# design.net
KiCad netlist of a schematic drawn in Altium Designer
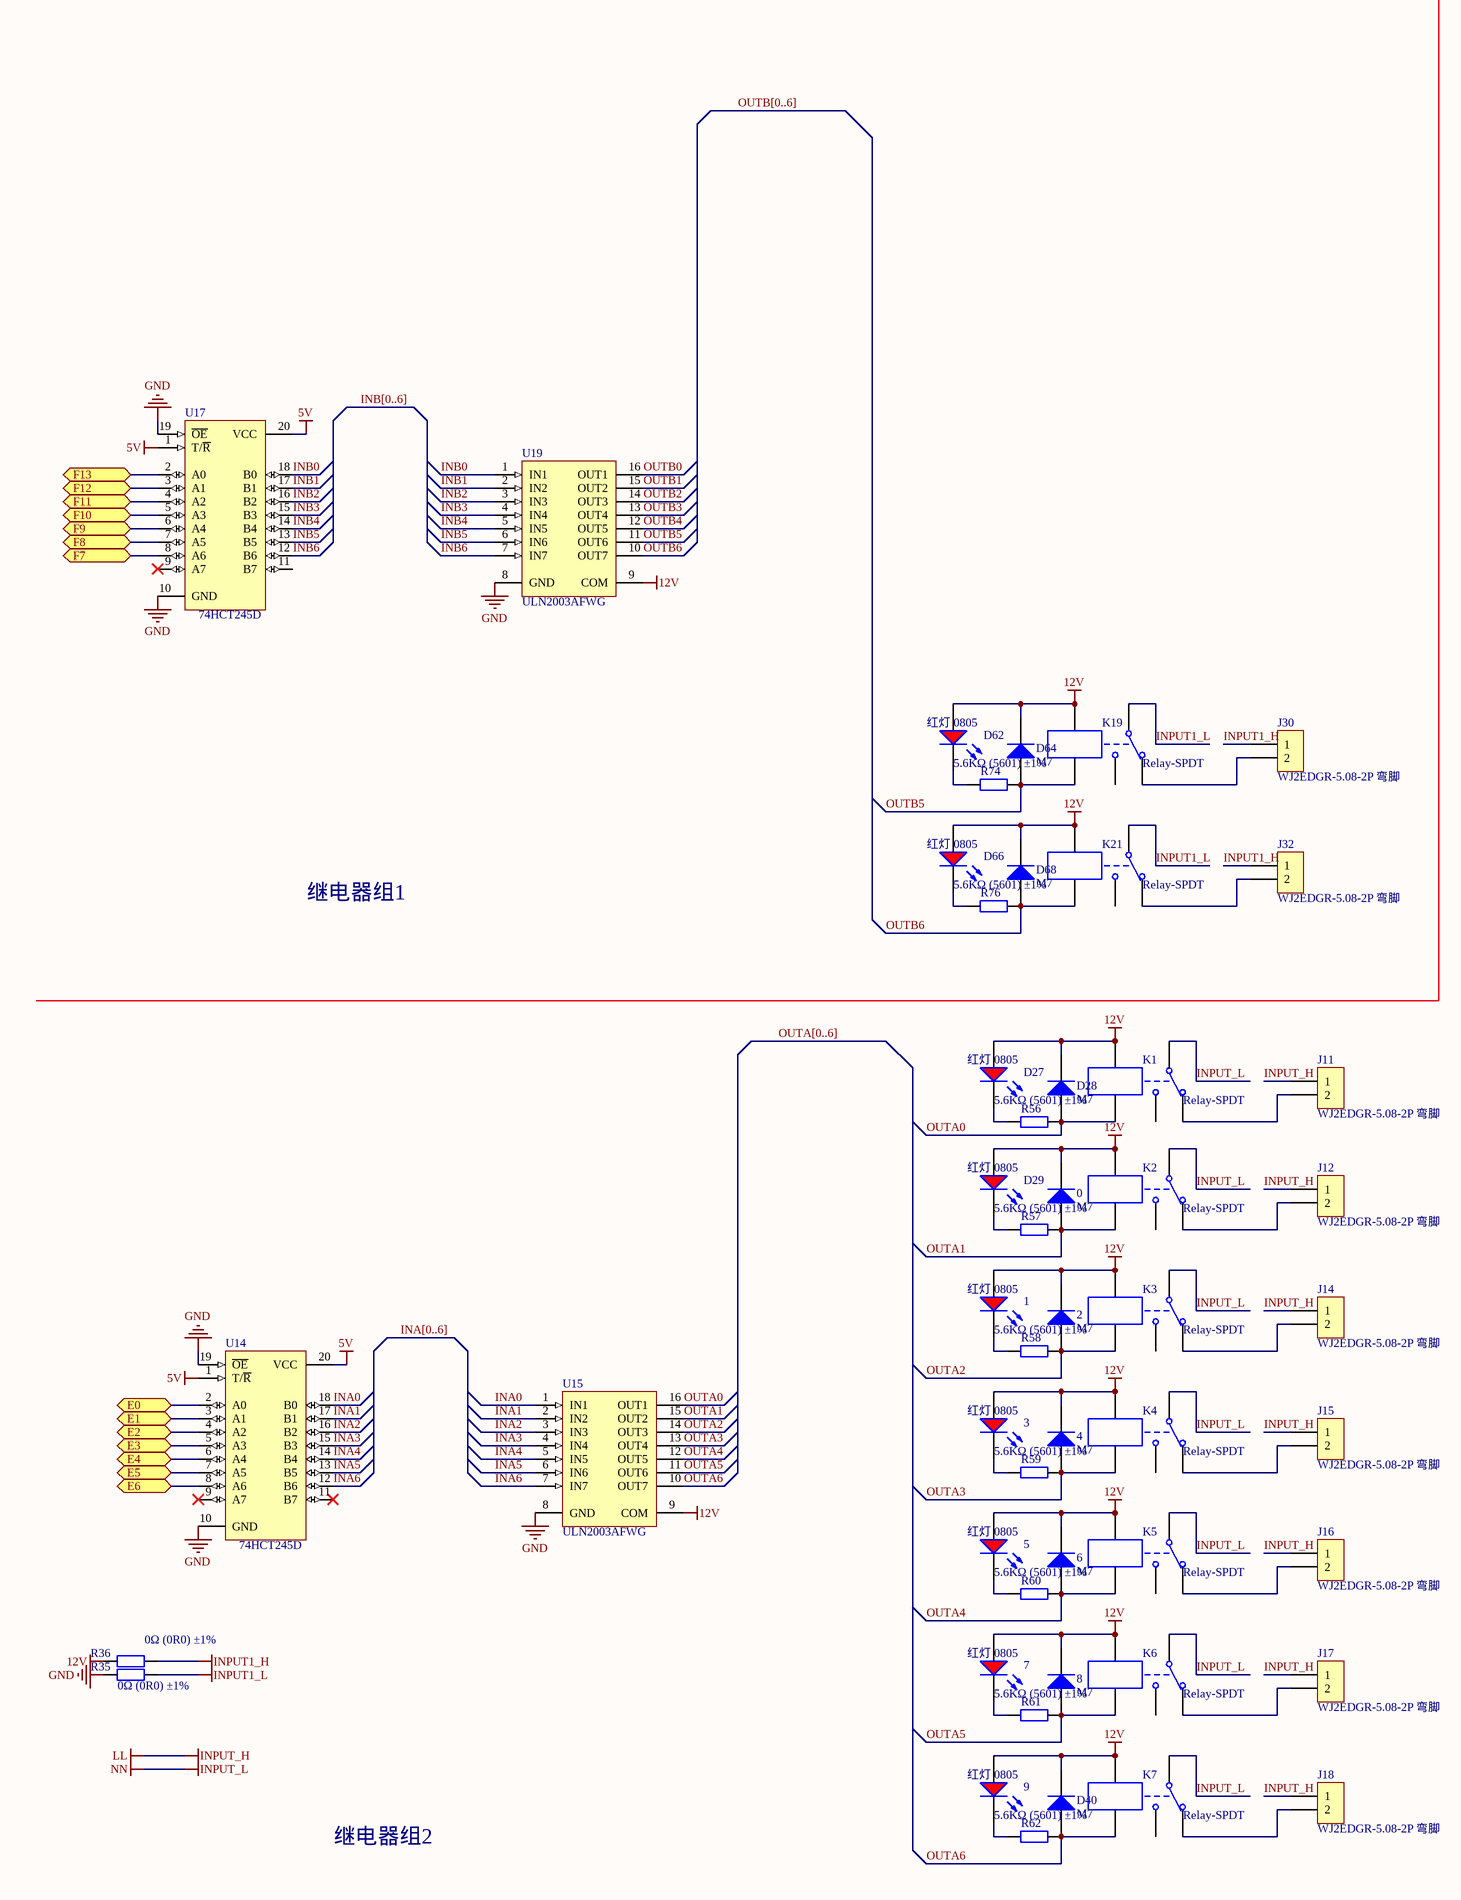
[diagram p0: 继电器驱动输出.SchDoc, left]
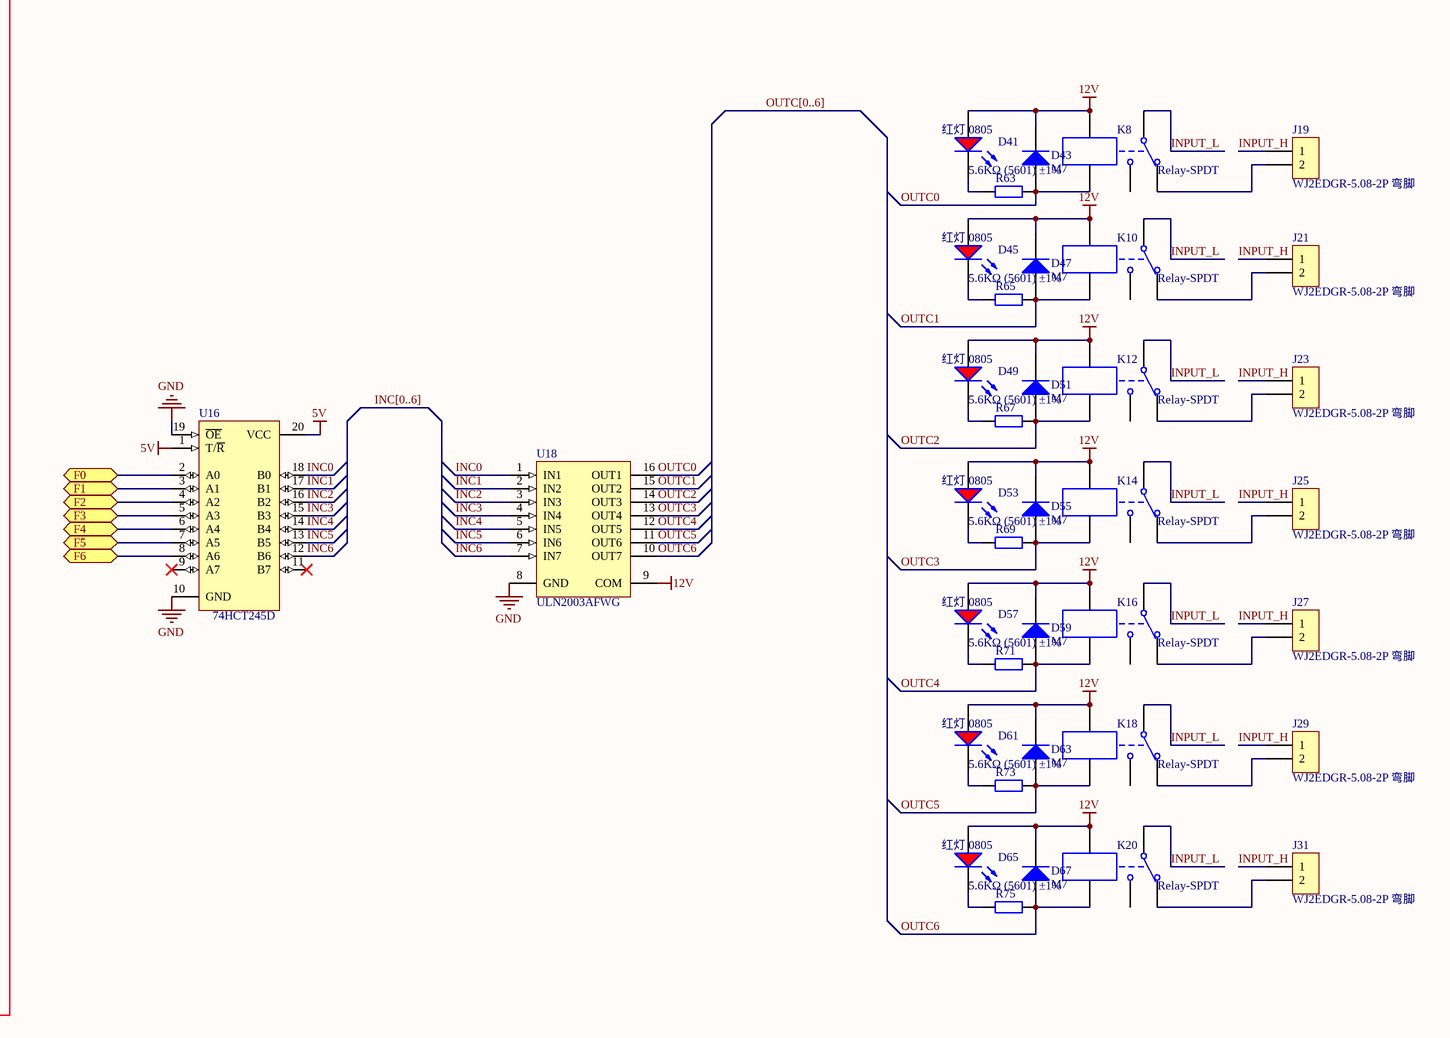
[diagram p1: 继电器驱动输出.SchDoc, right]

(export (version "E")
  (design (tool "Eeschema 10.0.6"))
  (components
    (comp (ref "0")
      (value "M7")
      (footprint "SMA(DO-214AC)_S1")
      (description "二极管")
      (libsource (lib "Diode") (part "SMA(DO-214AC) M7"))
    )
    (comp (ref "1")
      (value "红灯 0805")
      (footprint "0805_LED_S1")
      (description "发光二极管")
      (libsource (lib "LED") (part "0805 红灯"))
    )
    (comp (ref "2")
      (value "M7")
      (footprint "SMA(DO-214AC)_S1")
      (description "二极管")
      (libsource (lib "Diode") (part "SMA(DO-214AC) M7"))
    )
    (comp (ref "3")
      (value "红灯 0805")
      (footprint "0805_LED_S1")
      (description "发光二极管")
      (libsource (lib "LED") (part "0805 红灯"))
    )
    (comp (ref "4")
      (value "M7")
      (footprint "SMA(DO-214AC)_S1")
      (description "二极管")
      (libsource (lib "Diode") (part "SMA(DO-214AC) M7"))
    )
    (comp (ref "5")
      (value "红灯 0805")
      (footprint "0805_LED_S1")
      (description "发光二极管")
      (libsource (lib "LED") (part "0805 红灯"))
    )
    (comp (ref "6")
      (value "M7")
      (footprint "SMA(DO-214AC)_S1")
      (description "二极管")
      (libsource (lib "Diode") (part "SMA(DO-214AC) M7"))
    )
    (comp (ref "7")
      (value "红灯 0805")
      (footprint "0805_LED_S1")
      (description "发光二极管")
      (libsource (lib "LED") (part "0805 红灯"))
    )
    (comp (ref "8")
      (value "M7")
      (footprint "SMA(DO-214AC)_S1")
      (description "二极管")
      (libsource (lib "Diode") (part "SMA(DO-214AC) M7"))
    )
    (comp (ref "9")
      (value "红灯 0805")
      (footprint "0805_LED_S1")
      (description "发光二极管")
      (libsource (lib "LED") (part "0805 红灯"))
    )
    (comp (ref "D27")
      (value "红灯 0805")
      (footprint "0805_LED_S1")
      (description "发光二极管")
      (libsource (lib "LED") (part "0805 红灯"))
    )
    (comp (ref "D28")
      (value "M7")
      (footprint "SMA(DO-214AC)_S1")
      (description "二极管")
      (libsource (lib "Diode") (part "SMA(DO-214AC) M7"))
    )
    (comp (ref "D29")
      (value "红灯 0805")
      (footprint "0805_LED_S1")
      (description "发光二极管")
      (libsource (lib "LED") (part "0805 红灯"))
    )
    (comp (ref "D40")
      (value "M7")
      (footprint "SMA(DO-214AC)_S1")
      (description "二极管")
      (libsource (lib "Diode") (part "SMA(DO-214AC) M7"))
    )
    (comp (ref "D41")
      (value "红灯 0805")
      (footprint "0805_LED_S1")
      (description "发光二极管")
      (libsource (lib "LED") (part "0805 红灯"))
    )
    (comp (ref "D43")
      (value "M7")
      (footprint "SMA(DO-214AC)_S1")
      (description "二极管")
      (libsource (lib "Diode") (part "SMA(DO-214AC) M7"))
    )
    (comp (ref "D45")
      (value "红灯 0805")
      (footprint "0805_LED_S1")
      (description "发光二极管")
      (libsource (lib "LED") (part "0805 红灯"))
    )
    (comp (ref "D47")
      (value "M7")
      (footprint "SMA(DO-214AC)_S1")
      (description "二极管")
      (libsource (lib "Diode") (part "SMA(DO-214AC) M7"))
    )
    (comp (ref "D49")
      (value "红灯 0805")
      (footprint "0805_LED_S1")
      (description "发光二极管")
      (libsource (lib "LED") (part "0805 红灯"))
    )
    (comp (ref "D51")
      (value "M7")
      (footprint "SMA(DO-214AC)_S1")
      (description "二极管")
      (libsource (lib "Diode") (part "SMA(DO-214AC) M7"))
    )
    (comp (ref "D53")
      (value "红灯 0805")
      (footprint "0805_LED_S1")
      (description "发光二极管")
      (libsource (lib "LED") (part "0805 红灯"))
    )
    (comp (ref "D55")
      (value "M7")
      (footprint "SMA(DO-214AC)_S1")
      (description "二极管")
      (libsource (lib "Diode") (part "SMA(DO-214AC) M7"))
    )
    (comp (ref "D57")
      (value "红灯 0805")
      (footprint "0805_LED_S1")
      (description "发光二极管")
      (libsource (lib "LED") (part "0805 红灯"))
    )
    (comp (ref "D59")
      (value "M7")
      (footprint "SMA(DO-214AC)_S1")
      (description "二极管")
      (libsource (lib "Diode") (part "SMA(DO-214AC) M7"))
    )
    (comp (ref "D61")
      (value "红灯 0805")
      (footprint "0805_LED_S1")
      (description "发光二极管")
      (libsource (lib "LED") (part "0805 红灯"))
    )
    (comp (ref "D62")
      (value "红灯 0805")
      (footprint "0805_LED_S1")
      (description "发光二极管")
      (libsource (lib "LED") (part "0805 红灯"))
    )
    (comp (ref "D63")
      (value "M7")
      (footprint "SMA(DO-214AC)_S1")
      (description "二极管")
      (libsource (lib "Diode") (part "SMA(DO-214AC) M7"))
    )
    (comp (ref "D64")
      (value "M7")
      (footprint "SMA(DO-214AC)_S1")
      (description "二极管")
      (libsource (lib "Diode") (part "SMA(DO-214AC) M7"))
    )
    (comp (ref "D65")
      (value "红灯 0805")
      (footprint "0805_LED_S1")
      (description "发光二极管")
      (libsource (lib "LED") (part "0805 红灯"))
    )
    (comp (ref "D66")
      (value "红灯 0805")
      (footprint "0805_LED_S1")
      (description "发光二极管")
      (libsource (lib "LED") (part "0805 红灯"))
    )
    (comp (ref "D67")
      (value "M7")
      (footprint "SMA(DO-214AC)_S1")
      (description "二极管")
      (libsource (lib "Diode") (part "SMA(DO-214AC) M7"))
    )
    (comp (ref "D68")
      (value "M7")
      (footprint "SMA(DO-214AC)_S1")
      (description "二极管")
      (libsource (lib "Diode") (part "SMA(DO-214AC) M7"))
    )
    (comp (ref "J11")
      (value "WJ2EDGR-5.08-2P 弯脚")
      (footprint "Connector:WJ2EDGR-5.08-2")
      (description "2EDG连接器")
      (libsource (lib "Connector") (part "WJ2EDGR-5.08-2P 弯脚"))
    )
    (comp (ref "J12")
      (value "WJ2EDGR-5.08-2P 弯脚")
      (footprint "Connector:WJ2EDGR-5.08-2")
      (description "2EDG连接器")
      (libsource (lib "Connector") (part "WJ2EDGR-5.08-2P 弯脚"))
    )
    (comp (ref "J14")
      (value "WJ2EDGR-5.08-2P 弯脚")
      (footprint "Connector:WJ2EDGR-5.08-2")
      (description "2EDG连接器")
      (libsource (lib "Connector") (part "WJ2EDGR-5.08-2P 弯脚"))
    )
    (comp (ref "J15")
      (value "WJ2EDGR-5.08-2P 弯脚")
      (footprint "Connector:WJ2EDGR-5.08-2")
      (description "2EDG连接器")
      (libsource (lib "Connector") (part "WJ2EDGR-5.08-2P 弯脚"))
    )
    (comp (ref "J16")
      (value "WJ2EDGR-5.08-2P 弯脚")
      (footprint "Connector:WJ2EDGR-5.08-2")
      (description "2EDG连接器")
      (libsource (lib "Connector") (part "WJ2EDGR-5.08-2P 弯脚"))
    )
    (comp (ref "J17")
      (value "WJ2EDGR-5.08-2P 弯脚")
      (footprint "Connector:WJ2EDGR-5.08-2")
      (description "2EDG连接器")
      (libsource (lib "Connector") (part "WJ2EDGR-5.08-2P 弯脚"))
    )
    (comp (ref "J18")
      (value "WJ2EDGR-5.08-2P 弯脚")
      (footprint "Connector:WJ2EDGR-5.08-2")
      (description "2EDG连接器")
      (libsource (lib "Connector") (part "WJ2EDGR-5.08-2P 弯脚"))
    )
    (comp (ref "J19")
      (value "WJ2EDGR-5.08-2P 弯脚")
      (footprint "Connector:WJ2EDGR-5.08-2")
      (description "2EDG连接器")
      (libsource (lib "Connector") (part "WJ2EDGR-5.08-2P 弯脚"))
    )
    (comp (ref "J21")
      (value "WJ2EDGR-5.08-2P 弯脚")
      (footprint "Connector:WJ2EDGR-5.08-2")
      (description "2EDG连接器")
      (libsource (lib "Connector") (part "WJ2EDGR-5.08-2P 弯脚"))
    )
    (comp (ref "J23")
      (value "WJ2EDGR-5.08-2P 弯脚")
      (footprint "Connector:WJ2EDGR-5.08-2")
      (description "2EDG连接器")
      (libsource (lib "Connector") (part "WJ2EDGR-5.08-2P 弯脚"))
    )
    (comp (ref "J25")
      (value "WJ2EDGR-5.08-2P 弯脚")
      (footprint "Connector:WJ2EDGR-5.08-2")
      (description "2EDG连接器")
      (libsource (lib "Connector") (part "WJ2EDGR-5.08-2P 弯脚"))
    )
    (comp (ref "J27")
      (value "WJ2EDGR-5.08-2P 弯脚")
      (footprint "Connector:WJ2EDGR-5.08-2")
      (description "2EDG连接器")
      (libsource (lib "Connector") (part "WJ2EDGR-5.08-2P 弯脚"))
    )
    (comp (ref "J29")
      (value "WJ2EDGR-5.08-2P 弯脚")
      (footprint "Connector:WJ2EDGR-5.08-2")
      (description "2EDG连接器")
      (libsource (lib "Connector") (part "WJ2EDGR-5.08-2P 弯脚"))
    )
    (comp (ref "J30")
      (value "WJ2EDGR-5.08-2P 弯脚")
      (footprint "Connector:WJ2EDGR-5.08-2")
      (description "2EDG连接器")
      (libsource (lib "Connector") (part "WJ2EDGR-5.08-2P 弯脚"))
    )
    (comp (ref "J31")
      (value "WJ2EDGR-5.08-2P 弯脚")
      (footprint "Connector:WJ2EDGR-5.08-2")
      (description "2EDG连接器")
      (libsource (lib "Connector") (part "WJ2EDGR-5.08-2P 弯脚"))
    )
    (comp (ref "J32")
      (value "WJ2EDGR-5.08-2P 弯脚")
      (footprint "Connector:WJ2EDGR-5.08-2")
      (description "2EDG连接器")
      (libsource (lib "Connector") (part "WJ2EDGR-5.08-2P 弯脚"))
    )
    (comp (ref "K1")
      (value "Relay-SPDT")
      (footprint "继电器5脚")
      (description "Single-Pole Dual-Throw Relay")
      (fields (field (name "PUBLISHER") "Altium Limited"))
      (libsource (lib "Miscellaneous Devices") (part "Relay-SPDT"))
    )
    (comp (ref "K2")
      (value "Relay-SPDT")
      (footprint "继电器5脚")
      (description "Single-Pole Dual-Throw Relay")
      (fields (field (name "PUBLISHER") "Altium Limited"))
      (libsource (lib "Miscellaneous Devices") (part "Relay-SPDT"))
    )
    (comp (ref "K3")
      (value "Relay-SPDT")
      (footprint "继电器5脚")
      (description "Single-Pole Dual-Throw Relay")
      (fields (field (name "PUBLISHER") "Altium Limited"))
      (libsource (lib "Miscellaneous Devices") (part "Relay-SPDT"))
    )
    (comp (ref "K4")
      (value "Relay-SPDT")
      (footprint "继电器5脚")
      (description "Single-Pole Dual-Throw Relay")
      (fields (field (name "PUBLISHER") "Altium Limited"))
      (libsource (lib "Miscellaneous Devices") (part "Relay-SPDT"))
    )
    (comp (ref "K5")
      (value "Relay-SPDT")
      (footprint "继电器5脚")
      (description "Single-Pole Dual-Throw Relay")
      (fields (field (name "PUBLISHER") "Altium Limited"))
      (libsource (lib "Miscellaneous Devices") (part "Relay-SPDT"))
    )
    (comp (ref "K6")
      (value "Relay-SPDT")
      (footprint "继电器5脚")
      (description "Single-Pole Dual-Throw Relay")
      (fields (field (name "PUBLISHER") "Altium Limited"))
      (libsource (lib "Miscellaneous Devices") (part "Relay-SPDT"))
    )
    (comp (ref "K7")
      (value "Relay-SPDT")
      (footprint "继电器5脚")
      (description "Single-Pole Dual-Throw Relay")
      (fields (field (name "PUBLISHER") "Altium Limited"))
      (libsource (lib "Miscellaneous Devices") (part "Relay-SPDT"))
    )
    (comp (ref "K8")
      (value "Relay-SPDT")
      (footprint "继电器5脚")
      (description "Single-Pole Dual-Throw Relay")
      (fields (field (name "PUBLISHER") "Altium Limited"))
      (libsource (lib "Miscellaneous Devices") (part "Relay-SPDT"))
    )
    (comp (ref "K10")
      (value "Relay-SPDT")
      (footprint "继电器5脚")
      (description "Single-Pole Dual-Throw Relay")
      (fields (field (name "PUBLISHER") "Altium Limited"))
      (libsource (lib "Miscellaneous Devices") (part "Relay-SPDT"))
    )
    (comp (ref "K12")
      (value "Relay-SPDT")
      (footprint "继电器5脚")
      (description "Single-Pole Dual-Throw Relay")
      (fields (field (name "PUBLISHER") "Altium Limited"))
      (libsource (lib "Miscellaneous Devices") (part "Relay-SPDT"))
    )
    (comp (ref "K14")
      (value "Relay-SPDT")
      (footprint "继电器5脚")
      (description "Single-Pole Dual-Throw Relay")
      (fields (field (name "PUBLISHER") "Altium Limited"))
      (libsource (lib "Miscellaneous Devices") (part "Relay-SPDT"))
    )
    (comp (ref "K16")
      (value "Relay-SPDT")
      (footprint "继电器5脚")
      (description "Single-Pole Dual-Throw Relay")
      (fields (field (name "PUBLISHER") "Altium Limited"))
      (libsource (lib "Miscellaneous Devices") (part "Relay-SPDT"))
    )
    (comp (ref "K18")
      (value "Relay-SPDT")
      (footprint "继电器5脚")
      (description "Single-Pole Dual-Throw Relay")
      (fields (field (name "PUBLISHER") "Altium Limited"))
      (libsource (lib "Miscellaneous Devices") (part "Relay-SPDT"))
    )
    (comp (ref "K19")
      (value "Relay-SPDT")
      (footprint "继电器5脚")
      (description "Single-Pole Dual-Throw Relay")
      (fields (field (name "PUBLISHER") "Altium Limited"))
      (libsource (lib "Miscellaneous Devices") (part "Relay-SPDT"))
    )
    (comp (ref "K20")
      (value "Relay-SPDT")
      (footprint "继电器5脚")
      (description "Single-Pole Dual-Throw Relay")
      (fields (field (name "PUBLISHER") "Altium Limited"))
      (libsource (lib "Miscellaneous Devices") (part "Relay-SPDT"))
    )
    (comp (ref "K21")
      (value "Relay-SPDT")
      (footprint "继电器5脚")
      (description "Single-Pole Dual-Throw Relay")
      (fields (field (name "PUBLISHER") "Altium Limited"))
      (libsource (lib "Miscellaneous Devices") (part "Relay-SPDT"))
    )
    (comp (ref "R35")
      (value "0Ω (0R0) ±1%")
      (footprint "1206_R")
      (description "贴片电阻")
      (libsource (lib "RES") (part "1206 0Ω (0R0) 1%"))
    )
    (comp (ref "R36")
      (value "0Ω (0R0) ±1%")
      (footprint "1206_R")
      (description "贴片电阻")
      (libsource (lib "RES") (part "1206 0Ω (0R0) 1%"))
    )
    (comp (ref "R56")
      (value "5.6KΩ (5601) ±1%")
      (footprint "0805_R")
      (description "贴片电阻")
      (libsource (lib "RES") (part "0805 5.6KΩ (5601) 1%"))
    )
    (comp (ref "R57")
      (value "5.6KΩ (5601) ±1%")
      (footprint "0805_R")
      (description "贴片电阻")
      (libsource (lib "RES") (part "0805 5.6KΩ (5601) 1%"))
    )
    (comp (ref "R58")
      (value "5.6KΩ (5601) ±1%")
      (footprint "0805_R")
      (description "贴片电阻")
      (libsource (lib "RES") (part "0805 5.6KΩ (5601) 1%"))
    )
    (comp (ref "R59")
      (value "5.6KΩ (5601) ±1%")
      (footprint "0805_R")
      (description "贴片电阻")
      (libsource (lib "RES") (part "0805 5.6KΩ (5601) 1%"))
    )
    (comp (ref "R60")
      (value "5.6KΩ (5601) ±1%")
      (footprint "0805_R")
      (description "贴片电阻")
      (libsource (lib "RES") (part "0805 5.6KΩ (5601) 1%"))
    )
    (comp (ref "R61")
      (value "5.6KΩ (5601) ±1%")
      (footprint "0805_R")
      (description "贴片电阻")
      (libsource (lib "RES") (part "0805 5.6KΩ (5601) 1%"))
    )
    (comp (ref "R62")
      (value "5.6KΩ (5601) ±1%")
      (footprint "0805_R")
      (description "贴片电阻")
      (libsource (lib "RES") (part "0805 5.6KΩ (5601) 1%"))
    )
    (comp (ref "R63")
      (value "5.6KΩ (5601) ±1%")
      (footprint "0805_R")
      (description "贴片电阻")
      (libsource (lib "RES") (part "0805 5.6KΩ (5601) 1%"))
    )
    (comp (ref "R65")
      (value "5.6KΩ (5601) ±1%")
      (footprint "0805_R")
      (description "贴片电阻")
      (libsource (lib "RES") (part "0805 5.6KΩ (5601) 1%"))
    )
    (comp (ref "R67")
      (value "5.6KΩ (5601) ±1%")
      (footprint "0805_R")
      (description "贴片电阻")
      (libsource (lib "RES") (part "0805 5.6KΩ (5601) 1%"))
    )
    (comp (ref "R69")
      (value "5.6KΩ (5601) ±1%")
      (footprint "0805_R")
      (description "贴片电阻")
      (libsource (lib "RES") (part "0805 5.6KΩ (5601) 1%"))
    )
    (comp (ref "R71")
      (value "5.6KΩ (5601) ±1%")
      (footprint "0805_R")
      (description "贴片电阻")
      (libsource (lib "RES") (part "0805 5.6KΩ (5601) 1%"))
    )
    (comp (ref "R73")
      (value "5.6KΩ (5601) ±1%")
      (footprint "0805_R")
      (description "贴片电阻")
      (libsource (lib "RES") (part "0805 5.6KΩ (5601) 1%"))
    )
    (comp (ref "R74")
      (value "5.6KΩ (5601) ±1%")
      (footprint "0805_R")
      (description "贴片电阻")
      (libsource (lib "RES") (part "0805 5.6KΩ (5601) 1%"))
    )
    (comp (ref "R75")
      (value "5.6KΩ (5601) ±1%")
      (footprint "0805_R")
      (description "贴片电阻")
      (libsource (lib "RES") (part "0805 5.6KΩ (5601) 1%"))
    )
    (comp (ref "R76")
      (value "5.6KΩ (5601) ±1%")
      (footprint "0805_R")
      (description "贴片电阻")
      (libsource (lib "RES") (part "0805 5.6KΩ (5601) 1%"))
    )
    (comp (ref "U14")
      (value "74HCT245D")
      (footprint "SOIC-20_300mil")
      (description "74系列逻辑芯片")
      (libsource (lib "IC") (part "74HC245D_[C5625]"))
    )
    (comp (ref "U15")
      (value "ULN2003AFWG")
      (footprint "SOIC-16_150mil")
      (description "大电流驱动")
      (libsource (lib "IC") (part "ULN2003AFWG_[C5437]"))
    )
    (comp (ref "U16")
      (value "74HCT245D")
      (footprint "SOIC-20_300mil")
      (description "74系列逻辑芯片")
      (libsource (lib "IC") (part "74HC245D_[C5625]"))
    )
    (comp (ref "U17")
      (value "74HCT245D")
      (footprint "SOIC-20_300mil")
      (description "74系列逻辑芯片")
      (libsource (lib "IC") (part "74HC245D_[C5625]"))
    )
    (comp (ref "U18")
      (value "ULN2003AFWG")
      (footprint "SOIC-16_150mil")
      (description "大电流驱动")
      (libsource (lib "IC") (part "ULN2003AFWG_[C5437]"))
    )
    (comp (ref "U19")
      (value "ULN2003AFWG")
      (footprint "SOIC-16_150mil")
      (description "大电流驱动")
      (libsource (lib "IC") (part "ULN2003AFWG_[C5437]"))
    )
  )
  (nets
    (net (code "1") (name "/E0") (class "Default")
      (node (ref "U14") (pin "2") (pinfunction "A0_2") (pintype "bidirectional"))
    )
    (net (code "2") (name "/E1") (class "Default")
      (node (ref "U14") (pin "3") (pinfunction "A1_3") (pintype "bidirectional"))
    )
    (net (code "3") (name "/E2") (class "Default")
      (node (ref "U14") (pin "4") (pinfunction "A2_4") (pintype "bidirectional"))
    )
    (net (code "4") (name "/E3") (class "Default")
      (node (ref "U14") (pin "5") (pinfunction "A3_5") (pintype "bidirectional"))
    )
    (net (code "5") (name "/E4") (class "Default")
      (node (ref "U14") (pin "6") (pinfunction "A4_6") (pintype "bidirectional"))
    )
    (net (code "6") (name "/E5") (class "Default")
      (node (ref "U14") (pin "7") (pinfunction "A5_7") (pintype "bidirectional"))
    )
    (net (code "7") (name "/E6") (class "Default")
      (node (ref "U14") (pin "8") (pinfunction "A6_8") (pintype "bidirectional"))
    )
    (net (code "8") (name "/F0") (class "Default")
      (node (ref "U16") (pin "2") (pinfunction "A0_2") (pintype "bidirectional"))
    )
    (net (code "9") (name "/F1") (class "Default")
      (node (ref "U16") (pin "3") (pinfunction "A1_3") (pintype "bidirectional"))
    )
    (net (code "10") (name "/F2") (class "Default")
      (node (ref "U16") (pin "4") (pinfunction "A2_4") (pintype "bidirectional"))
    )
    (net (code "11") (name "/F3") (class "Default")
      (node (ref "U16") (pin "5") (pinfunction "A3_5") (pintype "bidirectional"))
    )
    (net (code "12") (name "/F4") (class "Default")
      (node (ref "U16") (pin "6") (pinfunction "A4_6") (pintype "bidirectional"))
    )
    (net (code "13") (name "/F5") (class "Default")
      (node (ref "U16") (pin "7") (pinfunction "A5_7") (pintype "bidirectional"))
    )
    (net (code "14") (name "/F6") (class "Default")
      (node (ref "U16") (pin "8") (pinfunction "A6_8") (pintype "bidirectional"))
    )
    (net (code "15") (name "/F7") (class "Default")
      (node (ref "U17") (pin "8") (pinfunction "A6_8") (pintype "bidirectional"))
    )
    (net (code "16") (name "/F8") (class "Default")
      (node (ref "U17") (pin "7") (pinfunction "A5_7") (pintype "bidirectional"))
    )
    (net (code "17") (name "/F9") (class "Default")
      (node (ref "U17") (pin "6") (pinfunction "A4_6") (pintype "bidirectional"))
    )
    (net (code "18") (name "/F10") (class "Default")
      (node (ref "U17") (pin "5") (pinfunction "A3_5") (pintype "bidirectional"))
    )
    (net (code "19") (name "/F11") (class "Default")
      (node (ref "U17") (pin "4") (pinfunction "A2_4") (pintype "bidirectional"))
    )
    (net (code "20") (name "/F12") (class "Default")
      (node (ref "U17") (pin "3") (pinfunction "A1_3") (pintype "bidirectional"))
    )
    (net (code "21") (name "/F13") (class "Default")
      (node (ref "U17") (pin "2") (pinfunction "A0_2") (pintype "bidirectional"))
    )
    (net (code "22") (name "/INA0") (class "Default")
      (node (ref "U14") (pin "18") (pinfunction "B0_18") (pintype "bidirectional"))
      (node (ref "U15") (pin "1") (pinfunction "IN1_1") (pintype "input"))
    )
    (net (code "23") (name "/INA1") (class "Default")
      (node (ref "U14") (pin "17") (pinfunction "B1_17") (pintype "bidirectional"))
      (node (ref "U15") (pin "2") (pinfunction "IN2_2") (pintype "input"))
    )
    (net (code "24") (name "/INA2") (class "Default")
      (node (ref "U14") (pin "16") (pinfunction "B2_16") (pintype "bidirectional"))
      (node (ref "U15") (pin "3") (pinfunction "IN3_3") (pintype "input"))
    )
    (net (code "25") (name "/INA3") (class "Default")
      (node (ref "U14") (pin "15") (pinfunction "B3_15") (pintype "bidirectional"))
      (node (ref "U15") (pin "4") (pinfunction "IN4_4") (pintype "input"))
    )
    (net (code "26") (name "/INA4") (class "Default")
      (node (ref "U14") (pin "14") (pinfunction "B4_14") (pintype "bidirectional"))
      (node (ref "U15") (pin "5") (pinfunction "IN5_5") (pintype "input"))
    )
    (net (code "27") (name "/INA5") (class "Default")
      (node (ref "U14") (pin "13") (pinfunction "B5_13") (pintype "bidirectional"))
      (node (ref "U15") (pin "6") (pinfunction "IN6_6") (pintype "input"))
    )
    (net (code "28") (name "/INA6") (class "Default")
      (node (ref "U14") (pin "12") (pinfunction "B6_12") (pintype "bidirectional"))
      (node (ref "U15") (pin "7") (pinfunction "IN7_7") (pintype "input"))
    )
    (net (code "30") (name "/INB0") (class "Default")
      (node (ref "U17") (pin "18") (pinfunction "B0_18") (pintype "bidirectional"))
      (node (ref "U19") (pin "1") (pinfunction "IN1_1") (pintype "input"))
    )
    (net (code "31") (name "/INB1") (class "Default")
      (node (ref "U17") (pin "17") (pinfunction "B1_17") (pintype "bidirectional"))
      (node (ref "U19") (pin "2") (pinfunction "IN2_2") (pintype "input"))
    )
    (net (code "32") (name "/INB2") (class "Default")
      (node (ref "U17") (pin "16") (pinfunction "B2_16") (pintype "bidirectional"))
      (node (ref "U19") (pin "3") (pinfunction "IN3_3") (pintype "input"))
    )
    (net (code "33") (name "/INB3") (class "Default")
      (node (ref "U17") (pin "15") (pinfunction "B3_15") (pintype "bidirectional"))
      (node (ref "U19") (pin "4") (pinfunction "IN4_4") (pintype "input"))
    )
    (net (code "34") (name "/INB4") (class "Default")
      (node (ref "U17") (pin "14") (pinfunction "B4_14") (pintype "bidirectional"))
      (node (ref "U19") (pin "5") (pinfunction "IN5_5") (pintype "input"))
    )
    (net (code "35") (name "/INB5") (class "Default")
      (node (ref "U17") (pin "13") (pinfunction "B5_13") (pintype "bidirectional"))
      (node (ref "U19") (pin "6") (pinfunction "IN6_6") (pintype "input"))
    )
    (net (code "36") (name "/INB6") (class "Default")
      (node (ref "U17") (pin "12") (pinfunction "B6_12") (pintype "bidirectional"))
      (node (ref "U19") (pin "7") (pinfunction "IN7_7") (pintype "input"))
    )
    (net (code "38") (name "/INC0") (class "Default")
      (node (ref "U16") (pin "18") (pinfunction "B0_18") (pintype "bidirectional"))
      (node (ref "U18") (pin "1") (pinfunction "IN1_1") (pintype "input"))
    )
    (net (code "39") (name "/INC1") (class "Default")
      (node (ref "U16") (pin "17") (pinfunction "B1_17") (pintype "bidirectional"))
      (node (ref "U18") (pin "2") (pinfunction "IN2_2") (pintype "input"))
    )
    (net (code "40") (name "/INC2") (class "Default")
      (node (ref "U16") (pin "16") (pinfunction "B2_16") (pintype "bidirectional"))
      (node (ref "U18") (pin "3") (pinfunction "IN3_3") (pintype "input"))
    )
    (net (code "41") (name "/INC3") (class "Default")
      (node (ref "U16") (pin "15") (pinfunction "B3_15") (pintype "bidirectional"))
      (node (ref "U18") (pin "4") (pinfunction "IN4_4") (pintype "input"))
    )
    (net (code "42") (name "/INC4") (class "Default")
      (node (ref "U16") (pin "14") (pinfunction "B4_14") (pintype "bidirectional"))
      (node (ref "U18") (pin "5") (pinfunction "IN5_5") (pintype "input"))
    )
    (net (code "43") (name "/INC5") (class "Default")
      (node (ref "U16") (pin "13") (pinfunction "B5_13") (pintype "bidirectional"))
      (node (ref "U18") (pin "6") (pinfunction "IN6_6") (pintype "input"))
    )
    (net (code "44") (name "/INC6") (class "Default")
      (node (ref "U16") (pin "12") (pinfunction "B6_12") (pintype "bidirectional"))
      (node (ref "U18") (pin "7") (pinfunction "IN7_7") (pintype "input"))
    )
    (net (code "46") (name "/OUTA0") (class "Default")
      (node (ref "D28") (pin "1") (pinfunction "A_1") (pintype "passive"))
      (node (ref "K1") (pin "5") (pinfunction "5_5") (pintype "passive"))
      (node (ref "R56") (pin "2") (pinfunction "2_2") (pintype "passive"))
      (node (ref "U15") (pin "16") (pinfunction "OUT1_16") (pintype "open_collector"))
    )
    (net (code "47") (name "/OUTA1") (class "Default")
      (node (ref "0") (pin "1") (pinfunction "A_1") (pintype "passive"))
      (node (ref "K2") (pin "5") (pinfunction "5_5") (pintype "passive"))
      (node (ref "R57") (pin "2") (pinfunction "2_2") (pintype "passive"))
      (node (ref "U15") (pin "15") (pinfunction "OUT2_15") (pintype "open_collector"))
    )
    (net (code "48") (name "/OUTA2") (class "Default")
      (node (ref "2") (pin "1") (pinfunction "A_1") (pintype "passive"))
      (node (ref "K3") (pin "5") (pinfunction "5_5") (pintype "passive"))
      (node (ref "R58") (pin "2") (pinfunction "2_2") (pintype "passive"))
      (node (ref "U15") (pin "14") (pinfunction "OUT3_14") (pintype "open_collector"))
    )
    (net (code "49") (name "/OUTA3") (class "Default")
      (node (ref "4") (pin "1") (pinfunction "A_1") (pintype "passive"))
      (node (ref "K4") (pin "5") (pinfunction "5_5") (pintype "passive"))
      (node (ref "R59") (pin "2") (pinfunction "2_2") (pintype "passive"))
      (node (ref "U15") (pin "13") (pinfunction "OUT4_13") (pintype "open_collector"))
    )
    (net (code "50") (name "/OUTA4") (class "Default")
      (node (ref "6") (pin "1") (pinfunction "A_1") (pintype "passive"))
      (node (ref "K5") (pin "5") (pinfunction "5_5") (pintype "passive"))
      (node (ref "R60") (pin "2") (pinfunction "2_2") (pintype "passive"))
      (node (ref "U15") (pin "12") (pinfunction "OUT5_12") (pintype "open_collector"))
    )
    (net (code "51") (name "/OUTA5") (class "Default")
      (node (ref "8") (pin "1") (pinfunction "A_1") (pintype "passive"))
      (node (ref "K6") (pin "5") (pinfunction "5_5") (pintype "passive"))
      (node (ref "R61") (pin "2") (pinfunction "2_2") (pintype "passive"))
      (node (ref "U15") (pin "11") (pinfunction "OUT6_11") (pintype "open_collector"))
    )
    (net (code "52") (name "/OUTA6") (class "Default")
      (node (ref "D40") (pin "1") (pinfunction "A_1") (pintype "passive"))
      (node (ref "K7") (pin "5") (pinfunction "5_5") (pintype "passive"))
      (node (ref "R62") (pin "2") (pinfunction "2_2") (pintype "passive"))
      (node (ref "U15") (pin "10") (pinfunction "OUT7_10") (pintype "open_collector"))
    )
    (net (code "54") (name "/OUTB0") (class "Default")
      (node (ref "U19") (pin "16") (pinfunction "OUT1_16") (pintype "open_collector"))
    )
    (net (code "55") (name "/OUTB1") (class "Default")
      (node (ref "U19") (pin "15") (pinfunction "OUT2_15") (pintype "open_collector"))
    )
    (net (code "56") (name "/OUTB2") (class "Default")
      (node (ref "U19") (pin "14") (pinfunction "OUT3_14") (pintype "open_collector"))
    )
    (net (code "57") (name "/OUTB3") (class "Default")
      (node (ref "U19") (pin "13") (pinfunction "OUT4_13") (pintype "open_collector"))
    )
    (net (code "58") (name "/OUTB4") (class "Default")
      (node (ref "U19") (pin "12") (pinfunction "OUT5_12") (pintype "open_collector"))
    )
    (net (code "59") (name "/OUTB5") (class "Default")
      (node (ref "D64") (pin "1") (pinfunction "A_1") (pintype "passive"))
      (node (ref "K19") (pin "5") (pinfunction "5_5") (pintype "passive"))
      (node (ref "R74") (pin "2") (pinfunction "2_2") (pintype "passive"))
      (node (ref "U19") (pin "11") (pinfunction "OUT6_11") (pintype "open_collector"))
    )
    (net (code "60") (name "/OUTB6") (class "Default")
      (node (ref "D68") (pin "1") (pinfunction "A_1") (pintype "passive"))
      (node (ref "K21") (pin "5") (pinfunction "5_5") (pintype "passive"))
      (node (ref "R76") (pin "2") (pinfunction "2_2") (pintype "passive"))
      (node (ref "U19") (pin "10") (pinfunction "OUT7_10") (pintype "open_collector"))
    )
    (net (code "62") (name "/OUTC0") (class "Default")
      (node (ref "D43") (pin "1") (pinfunction "A_1") (pintype "passive"))
      (node (ref "K8") (pin "5") (pinfunction "5_5") (pintype "passive"))
      (node (ref "R63") (pin "2") (pinfunction "2_2") (pintype "passive"))
      (node (ref "U18") (pin "16") (pinfunction "OUT1_16") (pintype "open_collector"))
    )
    (net (code "63") (name "/OUTC1") (class "Default")
      (node (ref "D47") (pin "1") (pinfunction "A_1") (pintype "passive"))
      (node (ref "K10") (pin "5") (pinfunction "5_5") (pintype "passive"))
      (node (ref "R65") (pin "2") (pinfunction "2_2") (pintype "passive"))
      (node (ref "U18") (pin "15") (pinfunction "OUT2_15") (pintype "open_collector"))
    )
    (net (code "64") (name "/OUTC2") (class "Default")
      (node (ref "D51") (pin "1") (pinfunction "A_1") (pintype "passive"))
      (node (ref "K12") (pin "5") (pinfunction "5_5") (pintype "passive"))
      (node (ref "R67") (pin "2") (pinfunction "2_2") (pintype "passive"))
      (node (ref "U18") (pin "14") (pinfunction "OUT3_14") (pintype "open_collector"))
    )
    (net (code "65") (name "/OUTC3") (class "Default")
      (node (ref "D55") (pin "1") (pinfunction "A_1") (pintype "passive"))
      (node (ref "K14") (pin "5") (pinfunction "5_5") (pintype "passive"))
      (node (ref "R69") (pin "2") (pinfunction "2_2") (pintype "passive"))
      (node (ref "U18") (pin "13") (pinfunction "OUT4_13") (pintype "open_collector"))
    )
    (net (code "66") (name "/OUTC4") (class "Default")
      (node (ref "D59") (pin "1") (pinfunction "A_1") (pintype "passive"))
      (node (ref "K16") (pin "5") (pinfunction "5_5") (pintype "passive"))
      (node (ref "R71") (pin "2") (pinfunction "2_2") (pintype "passive"))
      (node (ref "U18") (pin "12") (pinfunction "OUT5_12") (pintype "open_collector"))
    )
    (net (code "67") (name "/OUTC5") (class "Default")
      (node (ref "D63") (pin "1") (pinfunction "A_1") (pintype "passive"))
      (node (ref "K18") (pin "5") (pinfunction "5_5") (pintype "passive"))
      (node (ref "R73") (pin "2") (pinfunction "2_2") (pintype "passive"))
      (node (ref "U18") (pin "11") (pinfunction "OUT6_11") (pintype "open_collector"))
    )
    (net (code "68") (name "/OUTC6") (class "Default")
      (node (ref "D67") (pin "1") (pinfunction "A_1") (pintype "passive"))
      (node (ref "K20") (pin "5") (pinfunction "5_5") (pintype "passive"))
      (node (ref "R75") (pin "2") (pinfunction "2_2") (pintype "passive"))
      (node (ref "U18") (pin "10") (pinfunction "OUT7_10") (pintype "open_collector"))
    )
    (net (code "70") (name "5V") (class "Default")
      (node (ref "U14") (pin "1") (pinfunction "T/~{R}_1") (pintype "input"))
      (node (ref "U14") (pin "20") (pinfunction "VCC_20") (pintype "power_in"))
      (node (ref "U16") (pin "1") (pinfunction "T/~{R}_1") (pintype "input"))
      (node (ref "U16") (pin "20") (pinfunction "VCC_20") (pintype "power_in"))
      (node (ref "U17") (pin "1") (pinfunction "T/~{R}_1") (pintype "input"))
      (node (ref "U17") (pin "20") (pinfunction "VCC_20") (pintype "power_in"))
    )
    (net (code "71") (name "12V") (class "Default")
      (node (ref "0") (pin "2") (pinfunction "K_2") (pintype "passive"))
      (node (ref "1") (pin "A") (pinfunction "A_A") (pintype "passive"))
      (node (ref "2") (pin "2") (pinfunction "K_2") (pintype "passive"))
      (node (ref "3") (pin "A") (pinfunction "A_A") (pintype "passive"))
      (node (ref "4") (pin "2") (pinfunction "K_2") (pintype "passive"))
      (node (ref "5") (pin "A") (pinfunction "A_A") (pintype "passive"))
      (node (ref "6") (pin "2") (pinfunction "K_2") (pintype "passive"))
      (node (ref "7") (pin "A") (pinfunction "A_A") (pintype "passive"))
      (node (ref "8") (pin "2") (pinfunction "K_2") (pintype "passive"))
      (node (ref "9") (pin "A") (pinfunction "A_A") (pintype "passive"))
      (node (ref "D27") (pin "A") (pinfunction "A_A") (pintype "passive"))
      (node (ref "D28") (pin "2") (pinfunction "K_2") (pintype "passive"))
      (node (ref "D29") (pin "A") (pinfunction "A_A") (pintype "passive"))
      (node (ref "D40") (pin "2") (pinfunction "K_2") (pintype "passive"))
      (node (ref "D41") (pin "A") (pinfunction "A_A") (pintype "passive"))
      (node (ref "D43") (pin "2") (pinfunction "K_2") (pintype "passive"))
      (node (ref "D45") (pin "A") (pinfunction "A_A") (pintype "passive"))
      (node (ref "D47") (pin "2") (pinfunction "K_2") (pintype "passive"))
      (node (ref "D49") (pin "A") (pinfunction "A_A") (pintype "passive"))
      (node (ref "D51") (pin "2") (pinfunction "K_2") (pintype "passive"))
      (node (ref "D53") (pin "A") (pinfunction "A_A") (pintype "passive"))
      (node (ref "D55") (pin "2") (pinfunction "K_2") (pintype "passive"))
      (node (ref "D57") (pin "A") (pinfunction "A_A") (pintype "passive"))
      (node (ref "D59") (pin "2") (pinfunction "K_2") (pintype "passive"))
      (node (ref "D61") (pin "A") (pinfunction "A_A") (pintype "passive"))
      (node (ref "D62") (pin "A") (pinfunction "A_A") (pintype "passive"))
      (node (ref "D63") (pin "2") (pinfunction "K_2") (pintype "passive"))
      (node (ref "D64") (pin "2") (pinfunction "K_2") (pintype "passive"))
      (node (ref "D65") (pin "A") (pinfunction "A_A") (pintype "passive"))
      (node (ref "D66") (pin "A") (pinfunction "A_A") (pintype "passive"))
      (node (ref "D67") (pin "2") (pinfunction "K_2") (pintype "passive"))
      (node (ref "D68") (pin "2") (pinfunction "K_2") (pintype "passive"))
      (node (ref "K1") (pin "4") (pinfunction "4_4") (pintype "passive"))
      (node (ref "K10") (pin "4") (pinfunction "4_4") (pintype "passive"))
      (node (ref "K12") (pin "4") (pinfunction "4_4") (pintype "passive"))
      (node (ref "K14") (pin "4") (pinfunction "4_4") (pintype "passive"))
      (node (ref "K16") (pin "4") (pinfunction "4_4") (pintype "passive"))
      (node (ref "K18") (pin "4") (pinfunction "4_4") (pintype "passive"))
      (node (ref "K19") (pin "4") (pinfunction "4_4") (pintype "passive"))
      (node (ref "K2") (pin "4") (pinfunction "4_4") (pintype "passive"))
      (node (ref "K20") (pin "4") (pinfunction "4_4") (pintype "passive"))
      (node (ref "K21") (pin "4") (pinfunction "4_4") (pintype "passive"))
      (node (ref "K3") (pin "4") (pinfunction "4_4") (pintype "passive"))
      (node (ref "K4") (pin "4") (pinfunction "4_4") (pintype "passive"))
      (node (ref "K5") (pin "4") (pinfunction "4_4") (pintype "passive"))
      (node (ref "K6") (pin "4") (pinfunction "4_4") (pintype "passive"))
      (node (ref "K7") (pin "4") (pinfunction "4_4") (pintype "passive"))
      (node (ref "K8") (pin "4") (pinfunction "4_4") (pintype "passive"))
      (node (ref "R35") (pin "1") (pinfunction "1_1") (pintype "passive"))
      (node (ref "U15") (pin "9") (pinfunction "COM_9") (pintype "passive"))
      (node (ref "U18") (pin "9") (pinfunction "COM_9") (pintype "passive"))
      (node (ref "U19") (pin "9") (pinfunction "COM_9") (pintype "passive"))
    )
    (net (code "72") (name "GND") (class "Default")
      (node (ref "R36") (pin "1") (pinfunction "1_1") (pintype "passive"))
      (node (ref "U14") (pin "10") (pinfunction "GND_10") (pintype "power_in"))
      (node (ref "U14") (pin "19") (pinfunction "~{OE}_19") (pintype "input"))
      (node (ref "U15") (pin "8") (pinfunction "GND_8") (pintype "power_in"))
      (node (ref "U16") (pin "10") (pinfunction "GND_10") (pintype "power_in"))
      (node (ref "U16") (pin "19") (pinfunction "~{OE}_19") (pintype "input"))
      (node (ref "U17") (pin "10") (pinfunction "GND_10") (pintype "power_in"))
      (node (ref "U17") (pin "19") (pinfunction "~{OE}_19") (pintype "input"))
      (node (ref "U18") (pin "8") (pinfunction "GND_8") (pintype "power_in"))
      (node (ref "U19") (pin "8") (pinfunction "GND_8") (pintype "power_in"))
    )
    (net (code "73") (name "INPUT1_H") (class "Default")
      (node (ref "J30") (pin "1") (pinfunction "1_1") (pintype "passive"))
      (node (ref "J32") (pin "1") (pinfunction "1_1") (pintype "passive"))
      (node (ref "R35") (pin "2") (pinfunction "2_2") (pintype "passive"))
    )
    (net (code "74") (name "INPUT1_L") (class "Default")
      (node (ref "K19") (pin "1") (pinfunction "1_1") (pintype "passive"))
      (node (ref "K21") (pin "1") (pinfunction "1_1") (pintype "passive"))
      (node (ref "R36") (pin "2") (pinfunction "2_2") (pintype "passive"))
    )
    (net (code "75") (name "INPUT_H") (class "Default")
      (node (ref "J11") (pin "1") (pinfunction "1_1") (pintype "passive"))
      (node (ref "J12") (pin "1") (pinfunction "1_1") (pintype "passive"))
      (node (ref "J14") (pin "1") (pinfunction "1_1") (pintype "passive"))
      (node (ref "J15") (pin "1") (pinfunction "1_1") (pintype "passive"))
      (node (ref "J16") (pin "1") (pinfunction "1_1") (pintype "passive"))
      (node (ref "J17") (pin "1") (pinfunction "1_1") (pintype "passive"))
      (node (ref "J18") (pin "1") (pinfunction "1_1") (pintype "passive"))
      (node (ref "J19") (pin "1") (pinfunction "1_1") (pintype "passive"))
      (node (ref "J21") (pin "1") (pinfunction "1_1") (pintype "passive"))
      (node (ref "J23") (pin "1") (pinfunction "1_1") (pintype "passive"))
      (node (ref "J25") (pin "1") (pinfunction "1_1") (pintype "passive"))
      (node (ref "J27") (pin "1") (pinfunction "1_1") (pintype "passive"))
      (node (ref "J29") (pin "1") (pinfunction "1_1") (pintype "passive"))
      (node (ref "J31") (pin "1") (pinfunction "1_1") (pintype "passive"))
    )
    (net (code "76") (name "INPUT_L") (class "Default")
      (node (ref "K1") (pin "1") (pinfunction "1_1") (pintype "passive"))
      (node (ref "K10") (pin "1") (pinfunction "1_1") (pintype "passive"))
      (node (ref "K12") (pin "1") (pinfunction "1_1") (pintype "passive"))
      (node (ref "K14") (pin "1") (pinfunction "1_1") (pintype "passive"))
      (node (ref "K16") (pin "1") (pinfunction "1_1") (pintype "passive"))
      (node (ref "K18") (pin "1") (pinfunction "1_1") (pintype "passive"))
      (node (ref "K2") (pin "1") (pinfunction "1_1") (pintype "passive"))
      (node (ref "K20") (pin "1") (pinfunction "1_1") (pintype "passive"))
      (node (ref "K3") (pin "1") (pinfunction "1_1") (pintype "passive"))
      (node (ref "K4") (pin "1") (pinfunction "1_1") (pintype "passive"))
      (node (ref "K5") (pin "1") (pinfunction "1_1") (pintype "passive"))
      (node (ref "K6") (pin "1") (pinfunction "1_1") (pintype "passive"))
      (node (ref "K7") (pin "1") (pinfunction "1_1") (pintype "passive"))
      (node (ref "K8") (pin "1") (pinfunction "1_1") (pintype "passive"))
    )
    (net (code "77") (name "Net-(1-PadK)") (class "Default")
      (node (ref "1") (pin "K") (pinfunction "K_K") (pintype "passive"))
      (node (ref "R58") (pin "1") (pinfunction "1_1") (pintype "passive"))
    )
    (net (code "78") (name "Net-(3-PadK)") (class "Default")
      (node (ref "3") (pin "K") (pinfunction "K_K") (pintype "passive"))
      (node (ref "R59") (pin "1") (pinfunction "1_1") (pintype "passive"))
    )
    (net (code "79") (name "Net-(5-PadK)") (class "Default")
      (node (ref "5") (pin "K") (pinfunction "K_K") (pintype "passive"))
      (node (ref "R60") (pin "1") (pinfunction "1_1") (pintype "passive"))
    )
    (net (code "80") (name "Net-(7-PadK)") (class "Default")
      (node (ref "7") (pin "K") (pinfunction "K_K") (pintype "passive"))
      (node (ref "R61") (pin "1") (pinfunction "1_1") (pintype "passive"))
    )
    (net (code "81") (name "Net-(9-PadK)") (class "Default")
      (node (ref "9") (pin "K") (pinfunction "K_K") (pintype "passive"))
      (node (ref "R62") (pin "1") (pinfunction "1_1") (pintype "passive"))
    )
    (net (code "82") (name "Net-(D27-PadK)") (class "Default")
      (node (ref "D27") (pin "K") (pinfunction "K_K") (pintype "passive"))
      (node (ref "R56") (pin "1") (pinfunction "1_1") (pintype "passive"))
    )
    (net (code "83") (name "Net-(D29-PadK)") (class "Default")
      (node (ref "D29") (pin "K") (pinfunction "K_K") (pintype "passive"))
      (node (ref "R57") (pin "1") (pinfunction "1_1") (pintype "passive"))
    )
    (net (code "84") (name "Net-(D41-PadK)") (class "Default")
      (node (ref "D41") (pin "K") (pinfunction "K_K") (pintype "passive"))
      (node (ref "R63") (pin "1") (pinfunction "1_1") (pintype "passive"))
    )
    (net (code "85") (name "Net-(D45-PadK)") (class "Default")
      (node (ref "D45") (pin "K") (pinfunction "K_K") (pintype "passive"))
      (node (ref "R65") (pin "1") (pinfunction "1_1") (pintype "passive"))
    )
    (net (code "86") (name "Net-(D49-PadK)") (class "Default")
      (node (ref "D49") (pin "K") (pinfunction "K_K") (pintype "passive"))
      (node (ref "R67") (pin "1") (pinfunction "1_1") (pintype "passive"))
    )
    (net (code "87") (name "Net-(D53-PadK)") (class "Default")
      (node (ref "D53") (pin "K") (pinfunction "K_K") (pintype "passive"))
      (node (ref "R69") (pin "1") (pinfunction "1_1") (pintype "passive"))
    )
    (net (code "88") (name "Net-(D57-PadK)") (class "Default")
      (node (ref "D57") (pin "K") (pinfunction "K_K") (pintype "passive"))
      (node (ref "R71") (pin "1") (pinfunction "1_1") (pintype "passive"))
    )
    (net (code "89") (name "Net-(D61-PadK)") (class "Default")
      (node (ref "D61") (pin "K") (pinfunction "K_K") (pintype "passive"))
      (node (ref "R73") (pin "1") (pinfunction "1_1") (pintype "passive"))
    )
    (net (code "90") (name "Net-(D62-PadK)") (class "Default")
      (node (ref "D62") (pin "K") (pinfunction "K_K") (pintype "passive"))
      (node (ref "R74") (pin "1") (pinfunction "1_1") (pintype "passive"))
    )
    (net (code "91") (name "Net-(D65-PadK)") (class "Default")
      (node (ref "D65") (pin "K") (pinfunction "K_K") (pintype "passive"))
      (node (ref "R75") (pin "1") (pinfunction "1_1") (pintype "passive"))
    )
    (net (code "92") (name "Net-(D66-PadK)") (class "Default")
      (node (ref "D66") (pin "K") (pinfunction "K_K") (pintype "passive"))
      (node (ref "R76") (pin "1") (pinfunction "1_1") (pintype "passive"))
    )
    (net (code "93") (name "Net-(J11-Pad2)") (class "Default")
      (node (ref "J11") (pin "2") (pinfunction "2_2") (pintype "passive"))
      (node (ref "K1") (pin "2") (pinfunction "2_2") (pintype "passive"))
    )
    (net (code "94") (name "Net-(J12-Pad2)") (class "Default")
      (node (ref "J12") (pin "2") (pinfunction "2_2") (pintype "passive"))
      (node (ref "K2") (pin "2") (pinfunction "2_2") (pintype "passive"))
    )
    (net (code "95") (name "Net-(J14-Pad2)") (class "Default")
      (node (ref "J14") (pin "2") (pinfunction "2_2") (pintype "passive"))
      (node (ref "K3") (pin "2") (pinfunction "2_2") (pintype "passive"))
    )
    (net (code "96") (name "Net-(J15-Pad2)") (class "Default")
      (node (ref "J15") (pin "2") (pinfunction "2_2") (pintype "passive"))
      (node (ref "K4") (pin "2") (pinfunction "2_2") (pintype "passive"))
    )
    (net (code "97") (name "Net-(J16-Pad2)") (class "Default")
      (node (ref "J16") (pin "2") (pinfunction "2_2") (pintype "passive"))
      (node (ref "K5") (pin "2") (pinfunction "2_2") (pintype "passive"))
    )
    (net (code "98") (name "Net-(J17-Pad2)") (class "Default")
      (node (ref "J17") (pin "2") (pinfunction "2_2") (pintype "passive"))
      (node (ref "K6") (pin "2") (pinfunction "2_2") (pintype "passive"))
    )
    (net (code "99") (name "Net-(J18-Pad2)") (class "Default")
      (node (ref "J18") (pin "2") (pinfunction "2_2") (pintype "passive"))
      (node (ref "K7") (pin "2") (pinfunction "2_2") (pintype "passive"))
    )
    (net (code "100") (name "Net-(J19-Pad2)") (class "Default")
      (node (ref "J19") (pin "2") (pinfunction "2_2") (pintype "passive"))
      (node (ref "K8") (pin "2") (pinfunction "2_2") (pintype "passive"))
    )
    (net (code "101") (name "Net-(J21-Pad2)") (class "Default")
      (node (ref "J21") (pin "2") (pinfunction "2_2") (pintype "passive"))
      (node (ref "K10") (pin "2") (pinfunction "2_2") (pintype "passive"))
    )
    (net (code "102") (name "Net-(J23-Pad2)") (class "Default")
      (node (ref "J23") (pin "2") (pinfunction "2_2") (pintype "passive"))
      (node (ref "K12") (pin "2") (pinfunction "2_2") (pintype "passive"))
    )
    (net (code "103") (name "Net-(J25-Pad2)") (class "Default")
      (node (ref "J25") (pin "2") (pinfunction "2_2") (pintype "passive"))
      (node (ref "K14") (pin "2") (pinfunction "2_2") (pintype "passive"))
    )
    (net (code "104") (name "Net-(J27-Pad2)") (class "Default")
      (node (ref "J27") (pin "2") (pinfunction "2_2") (pintype "passive"))
      (node (ref "K16") (pin "2") (pinfunction "2_2") (pintype "passive"))
    )
    (net (code "105") (name "Net-(J29-Pad2)") (class "Default")
      (node (ref "J29") (pin "2") (pinfunction "2_2") (pintype "passive"))
      (node (ref "K18") (pin "2") (pinfunction "2_2") (pintype "passive"))
    )
    (net (code "106") (name "Net-(J30-Pad2)") (class "Default")
      (node (ref "J30") (pin "2") (pinfunction "2_2") (pintype "passive"))
      (node (ref "K19") (pin "2") (pinfunction "2_2") (pintype "passive"))
    )
    (net (code "107") (name "Net-(J31-Pad2)") (class "Default")
      (node (ref "J31") (pin "2") (pinfunction "2_2") (pintype "passive"))
      (node (ref "K20") (pin "2") (pinfunction "2_2") (pintype "passive"))
    )
    (net (code "108") (name "Net-(J32-Pad2)") (class "Default")
      (node (ref "J32") (pin "2") (pinfunction "2_2") (pintype "passive"))
      (node (ref "K21") (pin "2") (pinfunction "2_2") (pintype "passive"))
    )
    (net (code "109") (name "unconnected-(K1-Pad3)") (class "Default")
      (node (ref "K1") (pin "3") (pinfunction "3_3") (pintype "passive"))
    )
    (net (code "110") (name "unconnected-(K2-Pad3)") (class "Default")
      (node (ref "K2") (pin "3") (pinfunction "3_3") (pintype "passive"))
    )
    (net (code "111") (name "unconnected-(K3-Pad3)") (class "Default")
      (node (ref "K3") (pin "3") (pinfunction "3_3") (pintype "passive"))
    )
    (net (code "112") (name "unconnected-(K4-Pad3)") (class "Default")
      (node (ref "K4") (pin "3") (pinfunction "3_3") (pintype "passive"))
    )
    (net (code "113") (name "unconnected-(K5-Pad3)") (class "Default")
      (node (ref "K5") (pin "3") (pinfunction "3_3") (pintype "passive"))
    )
    (net (code "114") (name "unconnected-(K6-Pad3)") (class "Default")
      (node (ref "K6") (pin "3") (pinfunction "3_3") (pintype "passive"))
    )
    (net (code "115") (name "unconnected-(K7-Pad3)") (class "Default")
      (node (ref "K7") (pin "3") (pinfunction "3_3") (pintype "passive"))
    )
    (net (code "116") (name "unconnected-(K8-Pad3)") (class "Default")
      (node (ref "K8") (pin "3") (pinfunction "3_3") (pintype "passive"))
    )
    (net (code "117") (name "unconnected-(K10-Pad3)") (class "Default")
      (node (ref "K10") (pin "3") (pinfunction "3_3") (pintype "passive"))
    )
    (net (code "118") (name "unconnected-(K12-Pad3)") (class "Default")
      (node (ref "K12") (pin "3") (pinfunction "3_3") (pintype "passive"))
    )
    (net (code "119") (name "unconnected-(K14-Pad3)") (class "Default")
      (node (ref "K14") (pin "3") (pinfunction "3_3") (pintype "passive"))
    )
    (net (code "120") (name "unconnected-(K16-Pad3)") (class "Default")
      (node (ref "K16") (pin "3") (pinfunction "3_3") (pintype "passive"))
    )
    (net (code "121") (name "unconnected-(K18-Pad3)") (class "Default")
      (node (ref "K18") (pin "3") (pinfunction "3_3") (pintype "passive"))
    )
    (net (code "122") (name "unconnected-(K19-Pad3)") (class "Default")
      (node (ref "K19") (pin "3") (pinfunction "3_3") (pintype "passive"))
    )
    (net (code "123") (name "unconnected-(K20-Pad3)") (class "Default")
      (node (ref "K20") (pin "3") (pinfunction "3_3") (pintype "passive"))
    )
    (net (code "124") (name "unconnected-(K21-Pad3)") (class "Default")
      (node (ref "K21") (pin "3") (pinfunction "3_3") (pintype "passive"))
    )
    (net (code "125") (name "unconnected-(U14-A7-Pad9)") (class "Default")
      (node (ref "U14") (pin "9") (pinfunction "A7_9") (pintype "bidirectional+no_connect"))
    )
    (net (code "126") (name "unconnected-(U14-B7-Pad11)") (class "Default")
      (node (ref "U14") (pin "11") (pinfunction "B7_11") (pintype "bidirectional+no_connect"))
    )
    (net (code "127") (name "unconnected-(U16-A7-Pad9)") (class "Default")
      (node (ref "U16") (pin "9") (pinfunction "A7_9") (pintype "bidirectional+no_connect"))
    )
    (net (code "128") (name "unconnected-(U16-B7-Pad11)") (class "Default")
      (node (ref "U16") (pin "11") (pinfunction "B7_11") (pintype "bidirectional+no_connect"))
    )
    (net (code "129") (name "unconnected-(U17-A7-Pad9)") (class "Default")
      (node (ref "U17") (pin "9") (pinfunction "A7_9") (pintype "bidirectional+no_connect"))
    )
    (net (code "130") (name "unconnected-(U17-B7-Pad11)") (class "Default")
      (node (ref "U17") (pin "11") (pinfunction "B7_11") (pintype "bidirectional"))
    )
  )
)
